# register.net
KiCad netlist of a schematic drawn in EAGLE
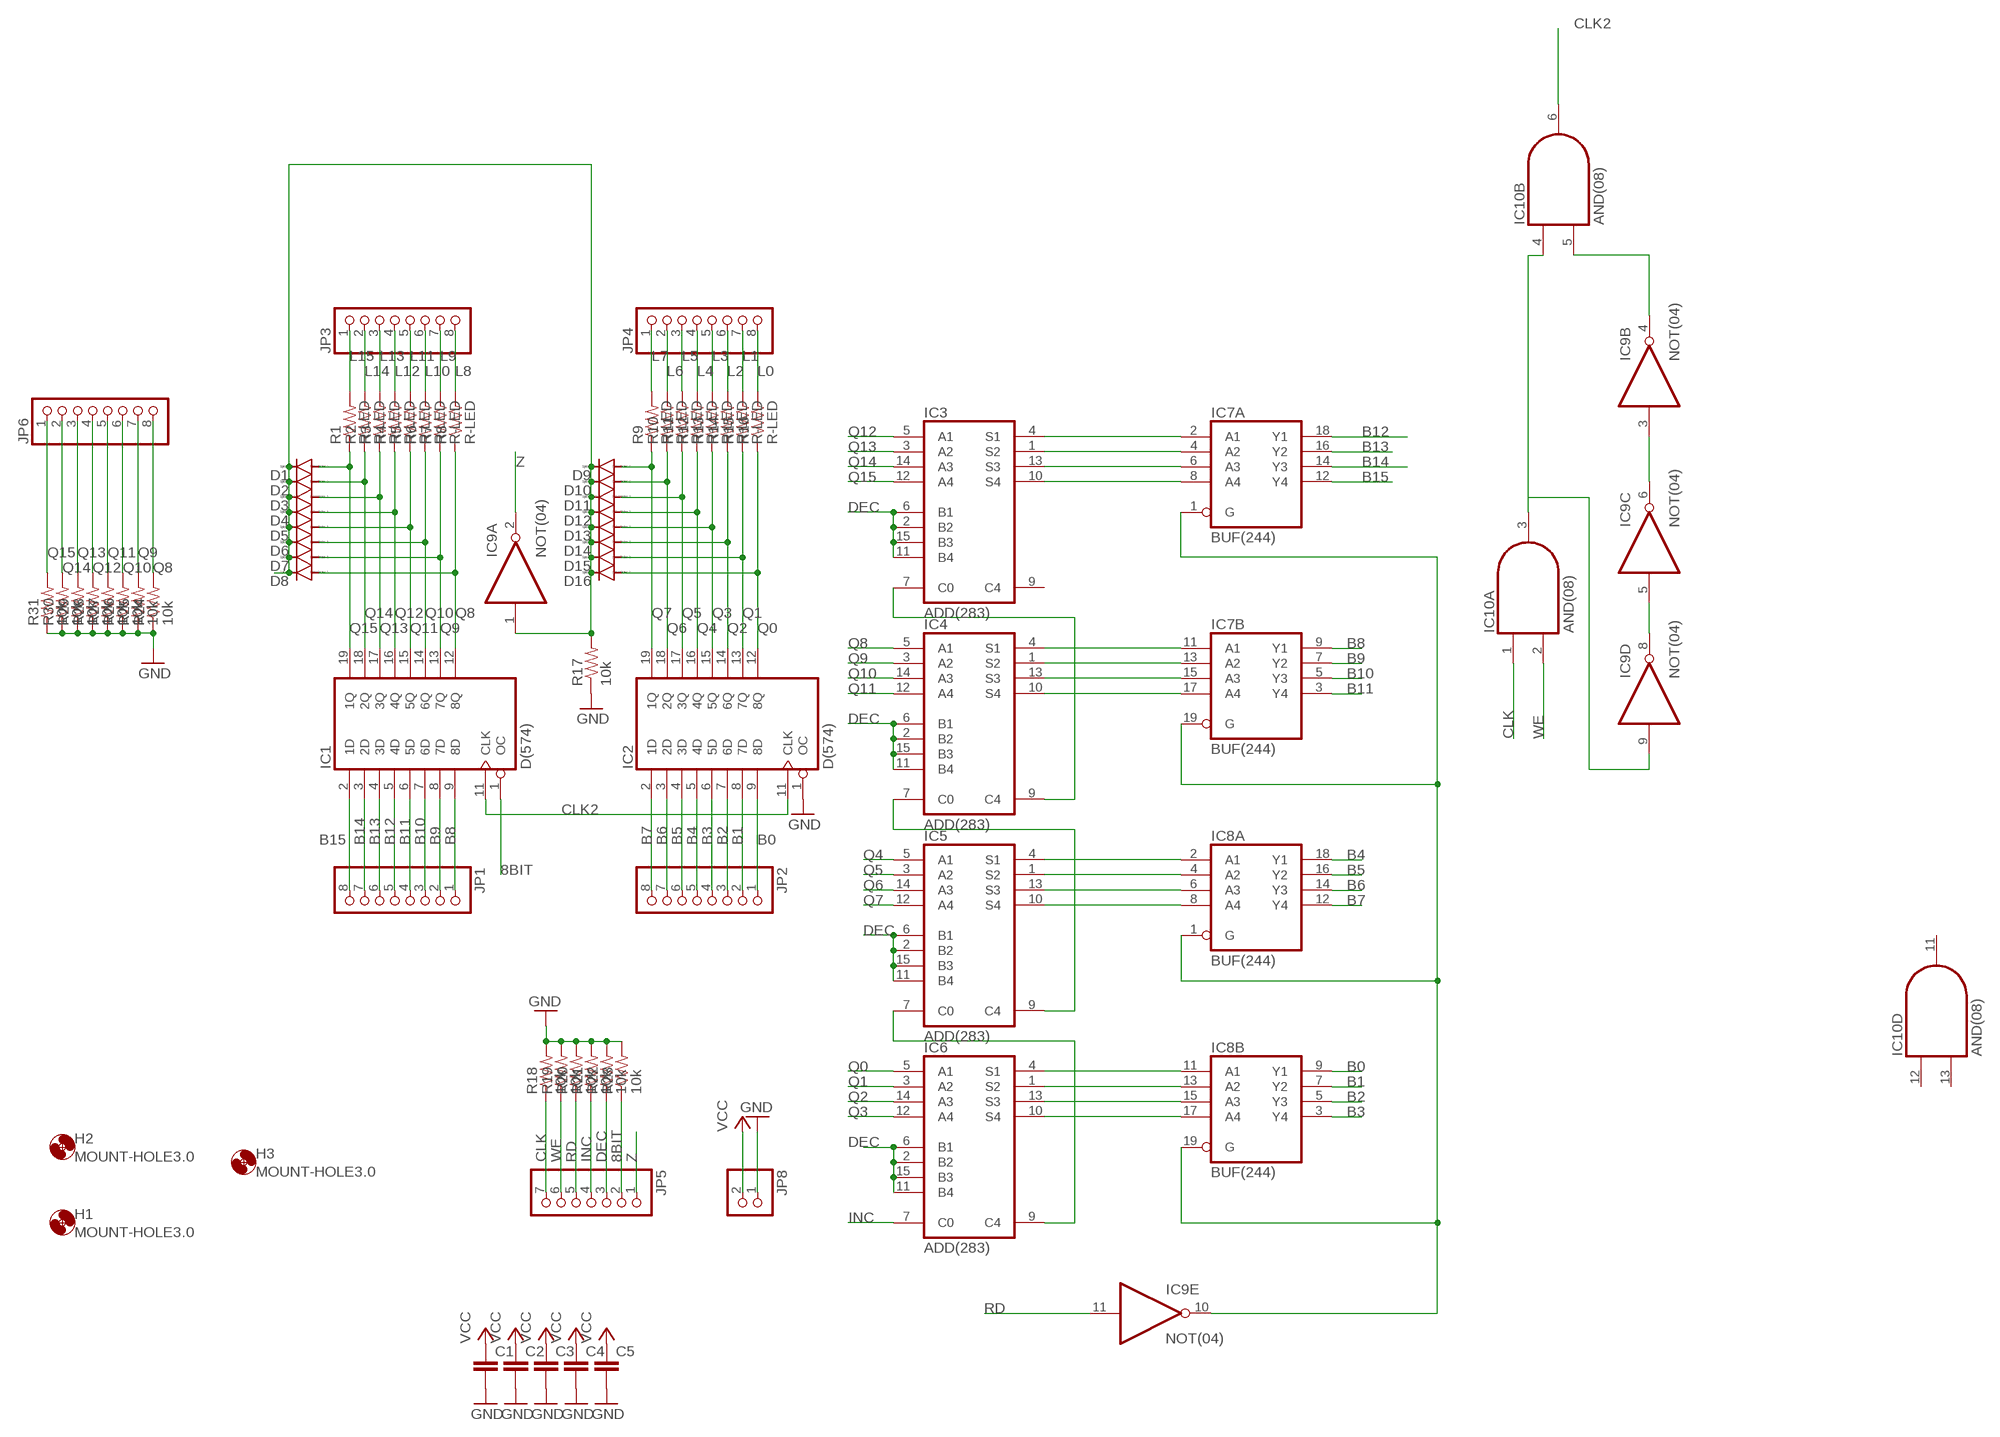
[diagram p0: schematic, sheet 1]

(export (version "E")
  (design (tool "Eeschema 10.0.6"))
  (components
    (comp (ref "C1")
      (value "C-Decouple")
      (footprint "eagle-import:C025-025X050")
      (libsource (lib "eagle-import") (part "C-EU025-025X050"))
    )
    (comp (ref "C2")
      (value "C-Decouple")
      (footprint "eagle-import:C025-025X050")
      (libsource (lib "eagle-import") (part "C-EU025-025X050"))
    )
    (comp (ref "C3")
      (value "C-Decouple")
      (footprint "eagle-import:C025-025X050")
      (libsource (lib "eagle-import") (part "C-EU025-025X050"))
    )
    (comp (ref "C4")
      (value "C-Decouple")
      (footprint "eagle-import:C025-025X050")
      (libsource (lib "eagle-import") (part "C-EU025-025X050"))
    )
    (comp (ref "C5")
      (value "C-Decouple")
      (footprint "eagle-import:C025-025X050")
      (libsource (lib "eagle-import") (part "C-EU025-025X050"))
    )
    (comp (ref "D1")
      (value "DIODE-D-7.5")
      (footprint "eagle-import:D-7.5")
      (libsource (lib "eagle-import") (part "DIODE-D-7.5"))
    )
    (comp (ref "D2")
      (value "DIODE-D-7.5")
      (footprint "eagle-import:D-7.5")
      (libsource (lib "eagle-import") (part "DIODE-D-7.5"))
    )
    (comp (ref "D3")
      (value "DIODE-D-7.5")
      (footprint "eagle-import:D-7.5")
      (libsource (lib "eagle-import") (part "DIODE-D-7.5"))
    )
    (comp (ref "D4")
      (value "DIODE-D-7.5")
      (footprint "eagle-import:D-7.5")
      (libsource (lib "eagle-import") (part "DIODE-D-7.5"))
    )
    (comp (ref "D5")
      (value "DIODE-D-7.5")
      (footprint "eagle-import:D-7.5")
      (libsource (lib "eagle-import") (part "DIODE-D-7.5"))
    )
    (comp (ref "D6")
      (value "DIODE-D-7.5")
      (footprint "eagle-import:D-7.5")
      (libsource (lib "eagle-import") (part "DIODE-D-7.5"))
    )
    (comp (ref "D7")
      (value "DIODE-D-7.5")
      (footprint "eagle-import:D-7.5")
      (libsource (lib "eagle-import") (part "DIODE-D-7.5"))
    )
    (comp (ref "D8")
      (value "DIODE-D-7.5")
      (footprint "eagle-import:D-7.5")
      (libsource (lib "eagle-import") (part "DIODE-D-7.5"))
    )
    (comp (ref "D9")
      (value "DIODE-D-7.5")
      (footprint "eagle-import:D-7.5")
      (libsource (lib "eagle-import") (part "DIODE-D-7.5"))
    )
    (comp (ref "D10")
      (value "DIODE-D-7.5")
      (footprint "eagle-import:D-7.5")
      (libsource (lib "eagle-import") (part "DIODE-D-7.5"))
    )
    (comp (ref "D11")
      (value "DIODE-D-7.5")
      (footprint "eagle-import:D-7.5")
      (libsource (lib "eagle-import") (part "DIODE-D-7.5"))
    )
    (comp (ref "D12")
      (value "DIODE-D-7.5")
      (footprint "eagle-import:D-7.5")
      (libsource (lib "eagle-import") (part "DIODE-D-7.5"))
    )
    (comp (ref "D13")
      (value "DIODE-D-7.5")
      (footprint "eagle-import:D-7.5")
      (libsource (lib "eagle-import") (part "DIODE-D-7.5"))
    )
    (comp (ref "D14")
      (value "DIODE-D-7.5")
      (footprint "eagle-import:D-7.5")
      (libsource (lib "eagle-import") (part "DIODE-D-7.5"))
    )
    (comp (ref "D15")
      (value "DIODE-D-7.5")
      (footprint "eagle-import:D-7.5")
      (libsource (lib "eagle-import") (part "DIODE-D-7.5"))
    )
    (comp (ref "D16")
      (value "DIODE-D-7.5")
      (footprint "eagle-import:D-7.5")
      (libsource (lib "eagle-import") (part "DIODE-D-7.5"))
    )
    (comp (ref "H1")
      (value "MOUNT-HOLE3.0")
      (footprint "eagle-import:3,0")
      (libsource (lib "eagle-import") (part "MOUNT-HOLE3.0"))
    )
    (comp (ref "H2")
      (value "MOUNT-HOLE3.0")
      (footprint "eagle-import:3,0")
      (libsource (lib "eagle-import") (part "MOUNT-HOLE3.0"))
    )
    (comp (ref "H3")
      (value "MOUNT-HOLE3.0")
      (footprint "eagle-import:3,0")
      (libsource (lib "eagle-import") (part "MOUNT-HOLE3.0"))
    )
    (comp (ref "IC1")
      (value "D(574)")
      (footprint "eagle-import:DIL20")
      (libsource (lib "eagle-import") (part "74574NAS"))
    )
    (comp (ref "IC2")
      (value "D(574)")
      (footprint "eagle-import:DIL20")
      (libsource (lib "eagle-import") (part "74574NAS"))
    )
    (comp (ref "IC3")
      (value "ADD(283)")
      (footprint "eagle-import:DIL16")
      (libsource (lib "eagle-import") (part "74283NAC"))
    )
    (comp (ref "IC4")
      (value "ADD(283)")
      (footprint "eagle-import:DIL16")
      (libsource (lib "eagle-import") (part "74283NAC"))
    )
    (comp (ref "IC5")
      (value "ADD(283)")
      (footprint "eagle-import:DIL16")
      (libsource (lib "eagle-import") (part "74283NAC"))
    )
    (comp (ref "IC6")
      (value "ADD(283)")
      (footprint "eagle-import:DIL16")
      (libsource (lib "eagle-import") (part "74283NAC"))
    )
    (comp (ref "IC7")
      (value "BUF(244)")
      (footprint "eagle-import:DIL20")
      (fields (field (name "MOUSER") "595-SN74HCT244NE4"))
      (libsource (lib "eagle-import") (part "74244NAC"))
    )
    (comp (ref "IC8")
      (value "BUF(244)")
      (footprint "eagle-import:DIL20")
      (fields (field (name "MOUSER") "595-SN74HCT244NE4"))
      (libsource (lib "eagle-import") (part "74244NAC"))
    )
    (comp (ref "IC9")
      (value "NOT(04)")
      (footprint "eagle-import:DIL14")
      (fields (field (name "MOUSER") "595-SN74HCT04NE4"))
      (libsource (lib "eagle-import") (part "7404NALS"))
    )
    (comp (ref "IC10")
      (value "AND(08)")
      (footprint "eagle-import:DIL14")
      (fields (field (name "MOUSER") "595-SN74HC08AN"))
      (libsource (lib "eagle-import") (part "7408NALS"))
    )
    (comp (ref "JP1")
      (value "PINHD-1X8")
      (footprint "eagle-import:1X08")
      (libsource (lib "eagle-import") (part "PINHD-1X8"))
    )
    (comp (ref "JP2")
      (value "PINHD-1X8")
      (footprint "eagle-import:1X08")
      (libsource (lib "eagle-import") (part "PINHD-1X8"))
    )
    (comp (ref "JP3")
      (value "PINHD-1X8")
      (footprint "eagle-import:1X08")
      (libsource (lib "eagle-import") (part "PINHD-1X8"))
    )
    (comp (ref "JP4")
      (value "PINHD-1X8")
      (footprint "eagle-import:1X08")
      (libsource (lib "eagle-import") (part "PINHD-1X8"))
    )
    (comp (ref "JP5")
      (value "PINHD-1X7")
      (footprint "eagle-import:1X07")
      (libsource (lib "eagle-import") (part "PINHD-1X7"))
    )
    (comp (ref "JP6")
      (value "PINHD-1X8")
      (footprint "eagle-import:1X08")
      (libsource (lib "eagle-import") (part "PINHD-1X8"))
    )
    (comp (ref "JP8")
      (value "PINHD-1X2")
      (footprint "eagle-import:1X02")
      (libsource (lib "eagle-import") (part "PINHD-1X2"))
    )
    (comp (ref "R1")
      (value "R-LED")
      (footprint "eagle-import:0204_7")
      (libsource (lib "eagle-import") (part "R-US_0204/7"))
    )
    (comp (ref "R2")
      (value "R-LED")
      (footprint "eagle-import:0204_7")
      (libsource (lib "eagle-import") (part "R-US_0204/7"))
    )
    (comp (ref "R3")
      (value "R-LED")
      (footprint "eagle-import:0204_7")
      (libsource (lib "eagle-import") (part "R-US_0204/7"))
    )
    (comp (ref "R4")
      (value "R-LED")
      (footprint "eagle-import:0204_7")
      (libsource (lib "eagle-import") (part "R-US_0204/7"))
    )
    (comp (ref "R5")
      (value "R-LED")
      (footprint "eagle-import:0204_7")
      (libsource (lib "eagle-import") (part "R-US_0204/7"))
    )
    (comp (ref "R6")
      (value "R-LED")
      (footprint "eagle-import:0204_7")
      (libsource (lib "eagle-import") (part "R-US_0204/7"))
    )
    (comp (ref "R7")
      (value "R-LED")
      (footprint "eagle-import:0204_7")
      (libsource (lib "eagle-import") (part "R-US_0204/7"))
    )
    (comp (ref "R8")
      (value "R-LED")
      (footprint "eagle-import:0204_7")
      (libsource (lib "eagle-import") (part "R-US_0204/7"))
    )
    (comp (ref "R9")
      (value "R-LED")
      (footprint "eagle-import:0204_7")
      (libsource (lib "eagle-import") (part "R-US_0204/7"))
    )
    (comp (ref "R10")
      (value "R-LED")
      (footprint "eagle-import:0204_7")
      (libsource (lib "eagle-import") (part "R-US_0204/7"))
    )
    (comp (ref "R11")
      (value "R-LED")
      (footprint "eagle-import:0204_7")
      (libsource (lib "eagle-import") (part "R-US_0204/7"))
    )
    (comp (ref "R12")
      (value "R-LED")
      (footprint "eagle-import:0204_7")
      (libsource (lib "eagle-import") (part "R-US_0204/7"))
    )
    (comp (ref "R13")
      (value "R-LED")
      (footprint "eagle-import:0204_7")
      (libsource (lib "eagle-import") (part "R-US_0204/7"))
    )
    (comp (ref "R14")
      (value "R-LED")
      (footprint "eagle-import:0204_7")
      (libsource (lib "eagle-import") (part "R-US_0204/7"))
    )
    (comp (ref "R15")
      (value "R-LED")
      (footprint "eagle-import:0204_7")
      (libsource (lib "eagle-import") (part "R-US_0204/7"))
    )
    (comp (ref "R16")
      (value "R-LED")
      (footprint "eagle-import:0204_7")
      (libsource (lib "eagle-import") (part "R-US_0204/7"))
    )
    (comp (ref "R17")
      (value "10k")
      (footprint "eagle-import:0204_7")
      (libsource (lib "eagle-import") (part "R-US_0204/7"))
    )
    (comp (ref "R18")
      (value "10k")
      (footprint "eagle-import:0204_7")
      (libsource (lib "eagle-import") (part "R-US_0204/7"))
    )
    (comp (ref "R19")
      (value "10k")
      (footprint "eagle-import:0204_7")
      (libsource (lib "eagle-import") (part "R-US_0204/7"))
    )
    (comp (ref "R20")
      (value "10k")
      (footprint "eagle-import:0204_7")
      (libsource (lib "eagle-import") (part "R-US_0204/7"))
    )
    (comp (ref "R21")
      (value "10k")
      (footprint "eagle-import:0204_7")
      (libsource (lib "eagle-import") (part "R-US_0204/7"))
    )
    (comp (ref "R22")
      (value "10k")
      (footprint "eagle-import:0204_7")
      (libsource (lib "eagle-import") (part "R-US_0204/7"))
    )
    (comp (ref "R23")
      (value "10k")
      (footprint "eagle-import:0204_7")
      (libsource (lib "eagle-import") (part "R-US_0204/7"))
    )
    (comp (ref "R24")
      (value "10k")
      (footprint "eagle-import:0204_7")
      (libsource (lib "eagle-import") (part "R-US_0204/7"))
    )
    (comp (ref "R25")
      (value "10k")
      (footprint "eagle-import:0204_7")
      (libsource (lib "eagle-import") (part "R-US_0204/7"))
    )
    (comp (ref "R26")
      (value "10k")
      (footprint "eagle-import:0204_7")
      (libsource (lib "eagle-import") (part "R-US_0204/7"))
    )
    (comp (ref "R27")
      (value "10k")
      (footprint "eagle-import:0204_7")
      (libsource (lib "eagle-import") (part "R-US_0204/7"))
    )
    (comp (ref "R28")
      (value "10k")
      (footprint "eagle-import:0204_7")
      (libsource (lib "eagle-import") (part "R-US_0204/7"))
    )
    (comp (ref "R29")
      (value "10k")
      (footprint "eagle-import:0204_7")
      (libsource (lib "eagle-import") (part "R-US_0204/7"))
    )
    (comp (ref "R30")
      (value "10k")
      (footprint "eagle-import:0204_7")
      (libsource (lib "eagle-import") (part "R-US_0204/7"))
    )
    (comp (ref "R31")
      (value "10k")
      (footprint "eagle-import:0204_7")
      (libsource (lib "eagle-import") (part "R-US_0204/7"))
    )
  )
  (nets
    (net (code "1") (name "/8BIT") (class "Default")
      (node (ref "IC1") (pin "1") (pinfunction "OC_1") (pintype "input"))
      (node (ref "JP5") (pin "2") (pinfunction "2_2") (pintype "passive"))
      (node (ref "R23") (pin "1") (pinfunction "1_1") (pintype "passive"))
    )
    (net (code "2") (name "/B0") (class "Default")
      (node (ref "IC2") (pin "9") (pinfunction "8D_9") (pintype "input"))
      (node (ref "IC8") (pin "9") (pinfunction "Y1_9") (pintype "tri_state"))
      (node (ref "JP2") (pin "1") (pinfunction "1_1") (pintype "passive"))
    )
    (net (code "3") (name "/B1") (class "Default")
      (node (ref "IC2") (pin "8") (pinfunction "7D_8") (pintype "input"))
      (node (ref "IC8") (pin "7") (pinfunction "Y2_7") (pintype "tri_state"))
      (node (ref "JP2") (pin "2") (pinfunction "2_2") (pintype "passive"))
    )
    (net (code "4") (name "/B2") (class "Default")
      (node (ref "IC2") (pin "7") (pinfunction "6D_7") (pintype "input"))
      (node (ref "IC8") (pin "5") (pinfunction "Y3_5") (pintype "tri_state"))
      (node (ref "JP2") (pin "3") (pinfunction "3_3") (pintype "passive"))
    )
    (net (code "5") (name "/B3") (class "Default")
      (node (ref "IC2") (pin "6") (pinfunction "5D_6") (pintype "input"))
      (node (ref "IC8") (pin "3") (pinfunction "Y4_3") (pintype "tri_state"))
      (node (ref "JP2") (pin "4") (pinfunction "4_4") (pintype "passive"))
    )
    (net (code "6") (name "/B4") (class "Default")
      (node (ref "IC2") (pin "5") (pinfunction "4D_5") (pintype "input"))
      (node (ref "IC8") (pin "18") (pinfunction "Y1_18") (pintype "tri_state"))
      (node (ref "JP2") (pin "5") (pinfunction "5_5") (pintype "passive"))
    )
    (net (code "7") (name "/B5") (class "Default")
      (node (ref "IC2") (pin "4") (pinfunction "3D_4") (pintype "input"))
      (node (ref "IC8") (pin "16") (pinfunction "Y2_16") (pintype "tri_state"))
      (node (ref "JP2") (pin "6") (pinfunction "6_6") (pintype "passive"))
    )
    (net (code "8") (name "/B6") (class "Default")
      (node (ref "IC2") (pin "3") (pinfunction "2D_3") (pintype "input"))
      (node (ref "IC8") (pin "14") (pinfunction "Y3_14") (pintype "tri_state"))
      (node (ref "JP2") (pin "7") (pinfunction "7_7") (pintype "passive"))
    )
    (net (code "9") (name "/B7") (class "Default")
      (node (ref "IC2") (pin "2") (pinfunction "1D_2") (pintype "input"))
      (node (ref "IC8") (pin "12") (pinfunction "Y4_12") (pintype "tri_state"))
      (node (ref "JP2") (pin "8") (pinfunction "8_8") (pintype "passive"))
    )
    (net (code "10") (name "/B8") (class "Default")
      (node (ref "IC1") (pin "9") (pinfunction "8D_9") (pintype "input"))
      (node (ref "IC7") (pin "9") (pinfunction "Y1_9") (pintype "tri_state"))
      (node (ref "JP1") (pin "1") (pinfunction "1_1") (pintype "passive"))
    )
    (net (code "11") (name "/B9") (class "Default")
      (node (ref "IC1") (pin "8") (pinfunction "7D_8") (pintype "input"))
      (node (ref "IC7") (pin "7") (pinfunction "Y2_7") (pintype "tri_state"))
      (node (ref "JP1") (pin "2") (pinfunction "2_2") (pintype "passive"))
    )
    (net (code "12") (name "/B10") (class "Default")
      (node (ref "IC1") (pin "7") (pinfunction "6D_7") (pintype "input"))
      (node (ref "IC7") (pin "5") (pinfunction "Y3_5") (pintype "tri_state"))
      (node (ref "JP1") (pin "3") (pinfunction "3_3") (pintype "passive"))
    )
    (net (code "13") (name "/B11") (class "Default")
      (node (ref "IC1") (pin "6") (pinfunction "5D_6") (pintype "input"))
      (node (ref "IC7") (pin "3") (pinfunction "Y4_3") (pintype "tri_state"))
      (node (ref "JP1") (pin "4") (pinfunction "4_4") (pintype "passive"))
    )
    (net (code "14") (name "/B12") (class "Default")
      (node (ref "IC1") (pin "5") (pinfunction "4D_5") (pintype "input"))
      (node (ref "IC7") (pin "18") (pinfunction "Y1_18") (pintype "tri_state"))
      (node (ref "JP1") (pin "5") (pinfunction "5_5") (pintype "passive"))
    )
    (net (code "15") (name "/B13") (class "Default")
      (node (ref "IC1") (pin "4") (pinfunction "3D_4") (pintype "input"))
      (node (ref "IC7") (pin "16") (pinfunction "Y2_16") (pintype "tri_state"))
      (node (ref "JP1") (pin "6") (pinfunction "6_6") (pintype "passive"))
    )
    (net (code "16") (name "/B14") (class "Default")
      (node (ref "IC1") (pin "3") (pinfunction "2D_3") (pintype "input"))
      (node (ref "IC7") (pin "14") (pinfunction "Y3_14") (pintype "tri_state"))
      (node (ref "JP1") (pin "7") (pinfunction "7_7") (pintype "passive"))
    )
    (net (code "17") (name "/B15") (class "Default")
      (node (ref "IC1") (pin "2") (pinfunction "1D_2") (pintype "input"))
      (node (ref "IC7") (pin "12") (pinfunction "Y4_12") (pintype "tri_state"))
      (node (ref "JP1") (pin "8") (pinfunction "8_8") (pintype "passive"))
    )
    (net (code "18") (name "/CLK") (class "Default")
      (node (ref "IC10") (pin "1") (pinfunction "I0_1") (pintype "input"))
      (node (ref "JP5") (pin "7") (pinfunction "7_7") (pintype "passive"))
      (node (ref "R18") (pin "1") (pinfunction "1_1") (pintype "passive"))
    )
    (net (code "19") (name "/CLK2") (class "Default")
      (node (ref "IC1") (pin "11") (pinfunction "CLK_11") (pintype "input"))
      (node (ref "IC10") (pin "6") (pinfunction "O_6") (pintype "output"))
      (node (ref "IC2") (pin "11") (pinfunction "CLK_11") (pintype "input"))
    )
    (net (code "20") (name "/DEC") (class "Default")
      (node (ref "IC3") (pin "11") (pinfunction "B4_11") (pintype "input"))
      (node (ref "IC3") (pin "15") (pinfunction "B3_15") (pintype "input"))
      (node (ref "IC3") (pin "2") (pinfunction "B2_2") (pintype "input"))
      (node (ref "IC3") (pin "6") (pinfunction "B1_6") (pintype "input"))
      (node (ref "IC4") (pin "11") (pinfunction "B4_11") (pintype "input"))
      (node (ref "IC4") (pin "15") (pinfunction "B3_15") (pintype "input"))
      (node (ref "IC4") (pin "2") (pinfunction "B2_2") (pintype "input"))
      (node (ref "IC4") (pin "6") (pinfunction "B1_6") (pintype "input"))
      (node (ref "IC5") (pin "11") (pinfunction "B4_11") (pintype "input"))
      (node (ref "IC5") (pin "15") (pinfunction "B3_15") (pintype "input"))
      (node (ref "IC5") (pin "2") (pinfunction "B2_2") (pintype "input"))
      (node (ref "IC5") (pin "6") (pinfunction "B1_6") (pintype "input"))
      (node (ref "IC6") (pin "11") (pinfunction "B4_11") (pintype "input"))
      (node (ref "IC6") (pin "15") (pinfunction "B3_15") (pintype "input"))
      (node (ref "IC6") (pin "2") (pinfunction "B2_2") (pintype "input"))
      (node (ref "IC6") (pin "6") (pinfunction "B1_6") (pintype "input"))
      (node (ref "JP5") (pin "3") (pinfunction "3_3") (pintype "passive"))
      (node (ref "R22") (pin "1") (pinfunction "1_1") (pintype "passive"))
    )
    (net (code "21") (name "/INC") (class "Default")
      (node (ref "IC6") (pin "7") (pinfunction "C0_7") (pintype "input"))
      (node (ref "JP5") (pin "4") (pinfunction "4_4") (pintype "passive"))
      (node (ref "R21") (pin "1") (pinfunction "1_1") (pintype "passive"))
    )
    (net (code "22") (name "/L0") (class "Default")
      (node (ref "JP4") (pin "8") (pinfunction "8_8") (pintype "passive"))
      (node (ref "R16") (pin "2") (pinfunction "2_2") (pintype "passive"))
    )
    (net (code "23") (name "/L1") (class "Default")
      (node (ref "JP4") (pin "7") (pinfunction "7_7") (pintype "passive"))
      (node (ref "R15") (pin "2") (pinfunction "2_2") (pintype "passive"))
    )
    (net (code "24") (name "/L2") (class "Default")
      (node (ref "JP4") (pin "6") (pinfunction "6_6") (pintype "passive"))
      (node (ref "R14") (pin "2") (pinfunction "2_2") (pintype "passive"))
    )
    (net (code "25") (name "/L3") (class "Default")
      (node (ref "JP4") (pin "5") (pinfunction "5_5") (pintype "passive"))
      (node (ref "R13") (pin "2") (pinfunction "2_2") (pintype "passive"))
    )
    (net (code "26") (name "/L4") (class "Default")
      (node (ref "JP4") (pin "4") (pinfunction "4_4") (pintype "passive"))
      (node (ref "R12") (pin "2") (pinfunction "2_2") (pintype "passive"))
    )
    (net (code "27") (name "/L5") (class "Default")
      (node (ref "JP4") (pin "3") (pinfunction "3_3") (pintype "passive"))
      (node (ref "R11") (pin "2") (pinfunction "2_2") (pintype "passive"))
    )
    (net (code "28") (name "/L6") (class "Default")
      (node (ref "JP4") (pin "2") (pinfunction "2_2") (pintype "passive"))
      (node (ref "R10") (pin "2") (pinfunction "2_2") (pintype "passive"))
    )
    (net (code "29") (name "/L7") (class "Default")
      (node (ref "JP4") (pin "1") (pinfunction "1_1") (pintype "passive"))
      (node (ref "R9") (pin "2") (pinfunction "2_2") (pintype "passive"))
    )
    (net (code "30") (name "/L8") (class "Default")
      (node (ref "JP3") (pin "8") (pinfunction "8_8") (pintype "passive"))
      (node (ref "R8") (pin "2") (pinfunction "2_2") (pintype "passive"))
    )
    (net (code "31") (name "/L9") (class "Default")
      (node (ref "JP3") (pin "7") (pinfunction "7_7") (pintype "passive"))
      (node (ref "R7") (pin "2") (pinfunction "2_2") (pintype "passive"))
    )
    (net (code "32") (name "/L10") (class "Default")
      (node (ref "JP3") (pin "6") (pinfunction "6_6") (pintype "passive"))
      (node (ref "R6") (pin "2") (pinfunction "2_2") (pintype "passive"))
    )
    (net (code "33") (name "/L11") (class "Default")
      (node (ref "JP3") (pin "5") (pinfunction "5_5") (pintype "passive"))
      (node (ref "R5") (pin "2") (pinfunction "2_2") (pintype "passive"))
    )
    (net (code "34") (name "/L12") (class "Default")
      (node (ref "JP3") (pin "4") (pinfunction "4_4") (pintype "passive"))
      (node (ref "R4") (pin "2") (pinfunction "2_2") (pintype "passive"))
    )
    (net (code "35") (name "/L13") (class "Default")
      (node (ref "JP3") (pin "3") (pinfunction "3_3") (pintype "passive"))
      (node (ref "R3") (pin "2") (pinfunction "2_2") (pintype "passive"))
    )
    (net (code "36") (name "/L14") (class "Default")
      (node (ref "JP3") (pin "2") (pinfunction "2_2") (pintype "passive"))
      (node (ref "R2") (pin "2") (pinfunction "2_2") (pintype "passive"))
    )
    (net (code "37") (name "/L15") (class "Default")
      (node (ref "JP3") (pin "1") (pinfunction "1_1") (pintype "passive"))
      (node (ref "R1") (pin "2") (pinfunction "2_2") (pintype "passive"))
    )
    (net (code "38") (name "/Q0") (class "Default")
      (node (ref "D16") (pin "A") (pinfunction "A_A") (pintype "passive"))
      (node (ref "IC2") (pin "12") (pinfunction "8Q_12") (pintype "tri_state"))
      (node (ref "IC6") (pin "5") (pinfunction "A1_5") (pintype "input"))
      (node (ref "R16") (pin "1") (pinfunction "1_1") (pintype "passive"))
    )
    (net (code "39") (name "/Q1") (class "Default")
      (node (ref "D15") (pin "A") (pinfunction "A_A") (pintype "passive"))
      (node (ref "IC2") (pin "13") (pinfunction "7Q_13") (pintype "tri_state"))
      (node (ref "IC6") (pin "3") (pinfunction "A2_3") (pintype "input"))
      (node (ref "R15") (pin "1") (pinfunction "1_1") (pintype "passive"))
    )
    (net (code "40") (name "/Q2") (class "Default")
      (node (ref "D14") (pin "A") (pinfunction "A_A") (pintype "passive"))
      (node (ref "IC2") (pin "14") (pinfunction "6Q_14") (pintype "tri_state"))
      (node (ref "IC6") (pin "14") (pinfunction "A3_14") (pintype "input"))
      (node (ref "R14") (pin "1") (pinfunction "1_1") (pintype "passive"))
    )
    (net (code "41") (name "/Q3") (class "Default")
      (node (ref "D13") (pin "A") (pinfunction "A_A") (pintype "passive"))
      (node (ref "IC2") (pin "15") (pinfunction "5Q_15") (pintype "tri_state"))
      (node (ref "IC6") (pin "12") (pinfunction "A4_12") (pintype "input"))
      (node (ref "R13") (pin "1") (pinfunction "1_1") (pintype "passive"))
    )
    (net (code "42") (name "/Q4") (class "Default")
      (node (ref "D12") (pin "A") (pinfunction "A_A") (pintype "passive"))
      (node (ref "IC2") (pin "16") (pinfunction "4Q_16") (pintype "tri_state"))
      (node (ref "IC5") (pin "5") (pinfunction "A1_5") (pintype "input"))
      (node (ref "R12") (pin "1") (pinfunction "1_1") (pintype "passive"))
    )
    (net (code "43") (name "/Q5") (class "Default")
      (node (ref "D11") (pin "A") (pinfunction "A_A") (pintype "passive"))
      (node (ref "IC2") (pin "17") (pinfunction "3Q_17") (pintype "tri_state"))
      (node (ref "IC5") (pin "3") (pinfunction "A2_3") (pintype "input"))
      (node (ref "R11") (pin "1") (pinfunction "1_1") (pintype "passive"))
    )
    (net (code "44") (name "/Q6") (class "Default")
      (node (ref "D10") (pin "A") (pinfunction "A_A") (pintype "passive"))
      (node (ref "IC2") (pin "18") (pinfunction "2Q_18") (pintype "tri_state"))
      (node (ref "IC5") (pin "14") (pinfunction "A3_14") (pintype "input"))
      (node (ref "R10") (pin "1") (pinfunction "1_1") (pintype "passive"))
    )
    (net (code "45") (name "/Q7") (class "Default")
      (node (ref "D9") (pin "A") (pinfunction "A_A") (pintype "passive"))
      (node (ref "IC2") (pin "19") (pinfunction "1Q_19") (pintype "tri_state"))
      (node (ref "IC5") (pin "12") (pinfunction "A4_12") (pintype "input"))
      (node (ref "R9") (pin "1") (pinfunction "1_1") (pintype "passive"))
    )
    (net (code "46") (name "/Q8") (class "Default")
      (node (ref "D8") (pin "A") (pinfunction "A_A") (pintype "passive"))
      (node (ref "IC1") (pin "12") (pinfunction "8Q_12") (pintype "tri_state"))
      (node (ref "IC4") (pin "5") (pinfunction "A1_5") (pintype "input"))
      (node (ref "JP6") (pin "8") (pinfunction "8_8") (pintype "passive"))
      (node (ref "R24") (pin "2") (pinfunction "2_2") (pintype "passive"))
      (node (ref "R8") (pin "1") (pinfunction "1_1") (pintype "passive"))
    )
    (net (code "47") (name "/Q9") (class "Default")
      (node (ref "D7") (pin "A") (pinfunction "A_A") (pintype "passive"))
      (node (ref "IC1") (pin "13") (pinfunction "7Q_13") (pintype "tri_state"))
      (node (ref "IC4") (pin "3") (pinfunction "A2_3") (pintype "input"))
      (node (ref "JP6") (pin "7") (pinfunction "7_7") (pintype "passive"))
      (node (ref "R25") (pin "2") (pinfunction "2_2") (pintype "passive"))
      (node (ref "R7") (pin "1") (pinfunction "1_1") (pintype "passive"))
    )
    (net (code "48") (name "/Q10") (class "Default")
      (node (ref "D6") (pin "A") (pinfunction "A_A") (pintype "passive"))
      (node (ref "IC1") (pin "14") (pinfunction "6Q_14") (pintype "tri_state"))
      (node (ref "IC4") (pin "14") (pinfunction "A3_14") (pintype "input"))
      (node (ref "JP6") (pin "6") (pinfunction "6_6") (pintype "passive"))
      (node (ref "R26") (pin "2") (pinfunction "2_2") (pintype "passive"))
      (node (ref "R6") (pin "1") (pinfunction "1_1") (pintype "passive"))
    )
    (net (code "49") (name "/Q11") (class "Default")
      (node (ref "D5") (pin "A") (pinfunction "A_A") (pintype "passive"))
      (node (ref "IC1") (pin "15") (pinfunction "5Q_15") (pintype "tri_state"))
      (node (ref "IC4") (pin "12") (pinfunction "A4_12") (pintype "input"))
      (node (ref "JP6") (pin "5") (pinfunction "5_5") (pintype "passive"))
      (node (ref "R27") (pin "2") (pinfunction "2_2") (pintype "passive"))
      (node (ref "R5") (pin "1") (pinfunction "1_1") (pintype "passive"))
    )
    (net (code "50") (name "/Q12") (class "Default")
      (node (ref "D4") (pin "A") (pinfunction "A_A") (pintype "passive"))
      (node (ref "IC1") (pin "16") (pinfunction "4Q_16") (pintype "tri_state"))
      (node (ref "IC3") (pin "5") (pinfunction "A1_5") (pintype "input"))
      (node (ref "JP6") (pin "4") (pinfunction "4_4") (pintype "passive"))
      (node (ref "R28") (pin "2") (pinfunction "2_2") (pintype "passive"))
      (node (ref "R4") (pin "1") (pinfunction "1_1") (pintype "passive"))
    )
    (net (code "51") (name "/Q13") (class "Default")
      (node (ref "D3") (pin "A") (pinfunction "A_A") (pintype "passive"))
      (node (ref "IC1") (pin "17") (pinfunction "3Q_17") (pintype "tri_state"))
      (node (ref "IC3") (pin "3") (pinfunction "A2_3") (pintype "input"))
      (node (ref "JP6") (pin "3") (pinfunction "3_3") (pintype "passive"))
      (node (ref "R29") (pin "2") (pinfunction "2_2") (pintype "passive"))
      (node (ref "R3") (pin "1") (pinfunction "1_1") (pintype "passive"))
    )
    (net (code "52") (name "/Q14") (class "Default")
      (node (ref "D2") (pin "A") (pinfunction "A_A") (pintype "passive"))
      (node (ref "IC1") (pin "18") (pinfunction "2Q_18") (pintype "tri_state"))
      (node (ref "IC3") (pin "14") (pinfunction "A3_14") (pintype "input"))
      (node (ref "JP6") (pin "2") (pinfunction "2_2") (pintype "passive"))
      (node (ref "R2") (pin "1") (pinfunction "1_1") (pintype "passive"))
      (node (ref "R30") (pin "2") (pinfunction "2_2") (pintype "passive"))
    )
    (net (code "53") (name "/Q15") (class "Default")
      (node (ref "D1") (pin "A") (pinfunction "A_A") (pintype "passive"))
      (node (ref "IC1") (pin "19") (pinfunction "1Q_19") (pintype "tri_state"))
      (node (ref "IC3") (pin "12") (pinfunction "A4_12") (pintype "input"))
      (node (ref "JP6") (pin "1") (pinfunction "1_1") (pintype "passive"))
      (node (ref "R1") (pin "1") (pinfunction "1_1") (pintype "passive"))
      (node (ref "R31") (pin "2") (pinfunction "2_2") (pintype "passive"))
    )
    (net (code "54") (name "/RD") (class "Default")
      (node (ref "IC9") (pin "11") (pinfunction "I_11") (pintype "input"))
      (node (ref "JP5") (pin "5") (pinfunction "5_5") (pintype "passive"))
      (node (ref "R20") (pin "1") (pinfunction "1_1") (pintype "passive"))
    )
    (net (code "55") (name "/WE") (class "Default")
      (node (ref "IC10") (pin "2") (pinfunction "I1_2") (pintype "input"))
      (node (ref "JP5") (pin "6") (pinfunction "6_6") (pintype "passive"))
      (node (ref "R19") (pin "1") (pinfunction "1_1") (pintype "passive"))
    )
    (net (code "56") (name "/Z") (class "Default")
      (node (ref "IC9") (pin "2") (pinfunction "O_2") (pintype "output"))
      (node (ref "JP5") (pin "1") (pinfunction "1_1") (pintype "passive"))
    )
    (net (code "57") (name "GND") (class "Default")
      (node (ref "C1") (pin "2") (pinfunction "2_2") (pintype "passive"))
      (node (ref "C2") (pin "2") (pinfunction "2_2") (pintype "passive"))
      (node (ref "C3") (pin "2") (pinfunction "2_2") (pintype "passive"))
      (node (ref "C4") (pin "2") (pinfunction "2_2") (pintype "passive"))
      (node (ref "C5") (pin "2") (pinfunction "2_2") (pintype "passive"))
      (node (ref "IC2") (pin "1") (pinfunction "OC_1") (pintype "input"))
      (node (ref "JP8") (pin "1") (pinfunction "1_1") (pintype "passive"))
      (node (ref "R17") (pin "1") (pinfunction "1_1") (pintype "passive"))
      (node (ref "R18") (pin "2") (pinfunction "2_2") (pintype "passive"))
      (node (ref "R19") (pin "2") (pinfunction "2_2") (pintype "passive"))
      (node (ref "R20") (pin "2") (pinfunction "2_2") (pintype "passive"))
      (node (ref "R21") (pin "2") (pinfunction "2_2") (pintype "passive"))
      (node (ref "R22") (pin "2") (pinfunction "2_2") (pintype "passive"))
      (node (ref "R23") (pin "2") (pinfunction "2_2") (pintype "passive"))
      (node (ref "R24") (pin "1") (pinfunction "1_1") (pintype "passive"))
      (node (ref "R25") (pin "1") (pinfunction "1_1") (pintype "passive"))
      (node (ref "R26") (pin "1") (pinfunction "1_1") (pintype "passive"))
      (node (ref "R27") (pin "1") (pinfunction "1_1") (pintype "passive"))
      (node (ref "R28") (pin "1") (pinfunction "1_1") (pintype "passive"))
      (node (ref "R29") (pin "1") (pinfunction "1_1") (pintype "passive"))
      (node (ref "R30") (pin "1") (pinfunction "1_1") (pintype "passive"))
      (node (ref "R31") (pin "1") (pinfunction "1_1") (pintype "passive"))
    )
    (net (code "58") (name "Net-(IC3A-C0)") (class "Default")
      (node (ref "IC3") (pin "7") (pinfunction "C0_7") (pintype "input"))
      (node (ref "IC4") (pin "9") (pinfunction "C4_9") (pintype "output"))
    )
    (net (code "59") (name "Net-(IC3A-S1)") (class "Default")
      (node (ref "IC3") (pin "4") (pinfunction "S1_4") (pintype "output"))
      (node (ref "IC7") (pin "2") (pinfunction "A1_2") (pintype "input"))
    )
    (net (code "60") (name "Net-(IC3A-S2)") (class "Default")
      (node (ref "IC3") (pin "1") (pinfunction "S2_1") (pintype "output"))
      (node (ref "IC7") (pin "4") (pinfunction "A2_4") (pintype "input"))
    )
    (net (code "61") (name "Net-(IC3A-S3)") (class "Default")
      (node (ref "IC3") (pin "13") (pinfunction "S3_13") (pintype "output"))
      (node (ref "IC7") (pin "6") (pinfunction "A3_6") (pintype "input"))
    )
    (net (code "62") (name "Net-(IC3A-S4)") (class "Default")
      (node (ref "IC3") (pin "10") (pinfunction "S4_10") (pintype "output"))
      (node (ref "IC7") (pin "8") (pinfunction "A4_8") (pintype "input"))
    )
    (net (code "63") (name "Net-(IC4A-C0)") (class "Default")
      (node (ref "IC4") (pin "7") (pinfunction "C0_7") (pintype "input"))
      (node (ref "IC5") (pin "9") (pinfunction "C4_9") (pintype "output"))
    )
    (net (code "64") (name "Net-(IC4A-S1)") (class "Default")
      (node (ref "IC4") (pin "4") (pinfunction "S1_4") (pintype "output"))
      (node (ref "IC7") (pin "11") (pinfunction "A1_11") (pintype "input"))
    )
    (net (code "65") (name "Net-(IC4A-S2)") (class "Default")
      (node (ref "IC4") (pin "1") (pinfunction "S2_1") (pintype "output"))
      (node (ref "IC7") (pin "13") (pinfunction "A2_13") (pintype "input"))
    )
    (net (code "66") (name "Net-(IC4A-S3)") (class "Default")
      (node (ref "IC4") (pin "13") (pinfunction "S3_13") (pintype "output"))
      (node (ref "IC7") (pin "15") (pinfunction "A3_15") (pintype "input"))
    )
    (net (code "67") (name "Net-(IC4A-S4)") (class "Default")
      (node (ref "IC4") (pin "10") (pinfunction "S4_10") (pintype "output"))
      (node (ref "IC7") (pin "17") (pinfunction "A4_17") (pintype "input"))
    )
    (net (code "68") (name "Net-(IC5A-C0)") (class "Default")
      (node (ref "IC5") (pin "7") (pinfunction "C0_7") (pintype "input"))
      (node (ref "IC6") (pin "9") (pinfunction "C4_9") (pintype "output"))
    )
    (net (code "69") (name "Net-(IC5A-S1)") (class "Default")
      (node (ref "IC5") (pin "4") (pinfunction "S1_4") (pintype "output"))
      (node (ref "IC8") (pin "2") (pinfunction "A1_2") (pintype "input"))
    )
    (net (code "70") (name "Net-(IC5A-S2)") (class "Default")
      (node (ref "IC5") (pin "1") (pinfunction "S2_1") (pintype "output"))
      (node (ref "IC8") (pin "4") (pinfunction "A2_4") (pintype "input"))
    )
    (net (code "71") (name "Net-(IC5A-S3)") (class "Default")
      (node (ref "IC5") (pin "13") (pinfunction "S3_13") (pintype "output"))
      (node (ref "IC8") (pin "6") (pinfunction "A3_6") (pintype "input"))
    )
    (net (code "72") (name "Net-(IC5A-S4)") (class "Default")
      (node (ref "IC5") (pin "10") (pinfunction "S4_10") (pintype "output"))
      (node (ref "IC8") (pin "8") (pinfunction "A4_8") (pintype "input"))
    )
    (net (code "73") (name "Net-(IC6A-S1)") (class "Default")
      (node (ref "IC6") (pin "4") (pinfunction "S1_4") (pintype "output"))
      (node (ref "IC8") (pin "11") (pinfunction "A1_11") (pintype "input"))
    )
    (net (code "74") (name "Net-(IC6A-S2)") (class "Default")
      (node (ref "IC6") (pin "1") (pinfunction "S2_1") (pintype "output"))
      (node (ref "IC8") (pin "13") (pinfunction "A2_13") (pintype "input"))
    )
    (net (code "75") (name "Net-(IC6A-S3)") (class "Default")
      (node (ref "IC6") (pin "13") (pinfunction "S3_13") (pintype "output"))
      (node (ref "IC8") (pin "15") (pinfunction "A3_15") (pintype "input"))
    )
    (net (code "76") (name "Net-(IC6A-S4)") (class "Default")
      (node (ref "IC6") (pin "10") (pinfunction "S4_10") (pintype "output"))
      (node (ref "IC8") (pin "17") (pinfunction "A4_17") (pintype "input"))
    )
    (net (code "77") (name "Net-(IC7A-G)") (class "Default")
      (node (ref "IC7") (pin "1") (pinfunction "G_1") (pintype "input"))
      (node (ref "IC7") (pin "19") (pinfunction "G_19") (pintype "input"))
      (node (ref "IC8") (pin "1") (pinfunction "G_1") (pintype "input"))
      (node (ref "IC8") (pin "19") (pinfunction "G_19") (pintype "input"))
      (node (ref "IC9") (pin "10") (pinfunction "O_10") (pintype "output"))
    )
    (net (code "78") (name "Net-(IC9A-I)") (class "Default")
      (node (ref "D1") (pin "C") (pinfunction "C_C") (pintype "passive"))
      (node (ref "D10") (pin "C") (pinfunction "C_C") (pintype "passive"))
      (node (ref "D11") (pin "C") (pinfunction "C_C") (pintype "passive"))
      (node (ref "D12") (pin "C") (pinfunction "C_C") (pintype "passive"))
      (node (ref "D13") (pin "C") (pinfunction "C_C") (pintype "passive"))
      (node (ref "D14") (pin "C") (pinfunction "C_C") (pintype "passive"))
      (node (ref "D15") (pin "C") (pinfunction "C_C") (pintype "passive"))
      (node (ref "D16") (pin "C") (pinfunction "C_C") (pintype "passive"))
      (node (ref "D2") (pin "C") (pinfunction "C_C") (pintype "passive"))
      (node (ref "D3") (pin "C") (pinfunction "C_C") (pintype "passive"))
      (node (ref "D4") (pin "C") (pinfunction "C_C") (pintype "passive"))
      (node (ref "D5") (pin "C") (pinfunction "C_C") (pintype "passive"))
      (node (ref "D6") (pin "C") (pinfunction "C_C") (pintype "passive"))
      (node (ref "D7") (pin "C") (pinfunction "C_C") (pintype "passive"))
      (node (ref "D8") (pin "C") (pinfunction "C_C") (pintype "passive"))
      (node (ref "D9") (pin "C") (pinfunction "C_C") (pintype "passive"))
      (node (ref "IC9") (pin "1") (pinfunction "I_1") (pintype "input"))
      (node (ref "R17") (pin "2") (pinfunction "2_2") (pintype "passive"))
    )
    (net (code "79") (name "Net-(IC9B-I)") (class "Default")
      (node (ref "IC9") (pin "3") (pinfunction "I_3") (pintype "input"))
      (node (ref "IC9") (pin "6") (pinfunction "O_6") (pintype "output"))
    )
    (net (code "80") (name "Net-(IC9C-I)") (class "Default")
      (node (ref "IC9") (pin "5") (pinfunction "I_5") (pintype "input"))
      (node (ref "IC9") (pin "8") (pinfunction "O_8") (pintype "output"))
    )
    (net (code "81") (name "Net-(IC10A-O)") (class "Default")
      (node (ref "IC10") (pin "3") (pinfunction "O_3") (pintype "output"))
      (node (ref "IC10") (pin "4") (pinfunction "I0_4") (pintype "input"))
      (node (ref "IC9") (pin "9") (pinfunction "I_9") (pintype "input"))
    )
    (net (code "82") (name "Net-(IC10B-I1)") (class "Default")
      (node (ref "IC10") (pin "5") (pinfunction "I1_5") (pintype "input"))
      (node (ref "IC9") (pin "4") (pinfunction "O_4") (pintype "output"))
    )
    (net (code "83") (name "VCC") (class "Default")
      (node (ref "C1") (pin "1") (pinfunction "1_1") (pintype "passive"))
      (node (ref "C2") (pin "1") (pinfunction "1_1") (pintype "passive"))
      (node (ref "C3") (pin "1") (pinfunction "1_1") (pintype "passive"))
      (node (ref "C4") (pin "1") (pinfunction "1_1") (pintype "passive"))
      (node (ref "C5") (pin "1") (pinfunction "1_1") (pintype "passive"))
      (node (ref "JP8") (pin "2") (pinfunction "2_2") (pintype "passive"))
    )
    (net (code "84") (name "unconnected-(IC3A-C4-Pad9)") (class "Default")
      (node (ref "IC3") (pin "9") (pinfunction "C4_9") (pintype "output"))
    )
    (net (code "85") (name "unconnected-(IC10D-I0-Pad12)") (class "Default")
      (node (ref "IC10") (pin "12") (pinfunction "I0_12") (pintype "input"))
    )
    (net (code "86") (name "unconnected-(IC10D-I1-Pad13)") (class "Default")
      (node (ref "IC10") (pin "13") (pinfunction "I1_13") (pintype "input"))
    )
    (net (code "87") (name "unconnected-(IC10D-O-Pad11)") (class "Default")
      (node (ref "IC10") (pin "11") (pinfunction "O_11") (pintype "output"))
    )
  )
)
